# 02_PCIE.net
KiCad netlist of a schematic drawn in Altium Designer
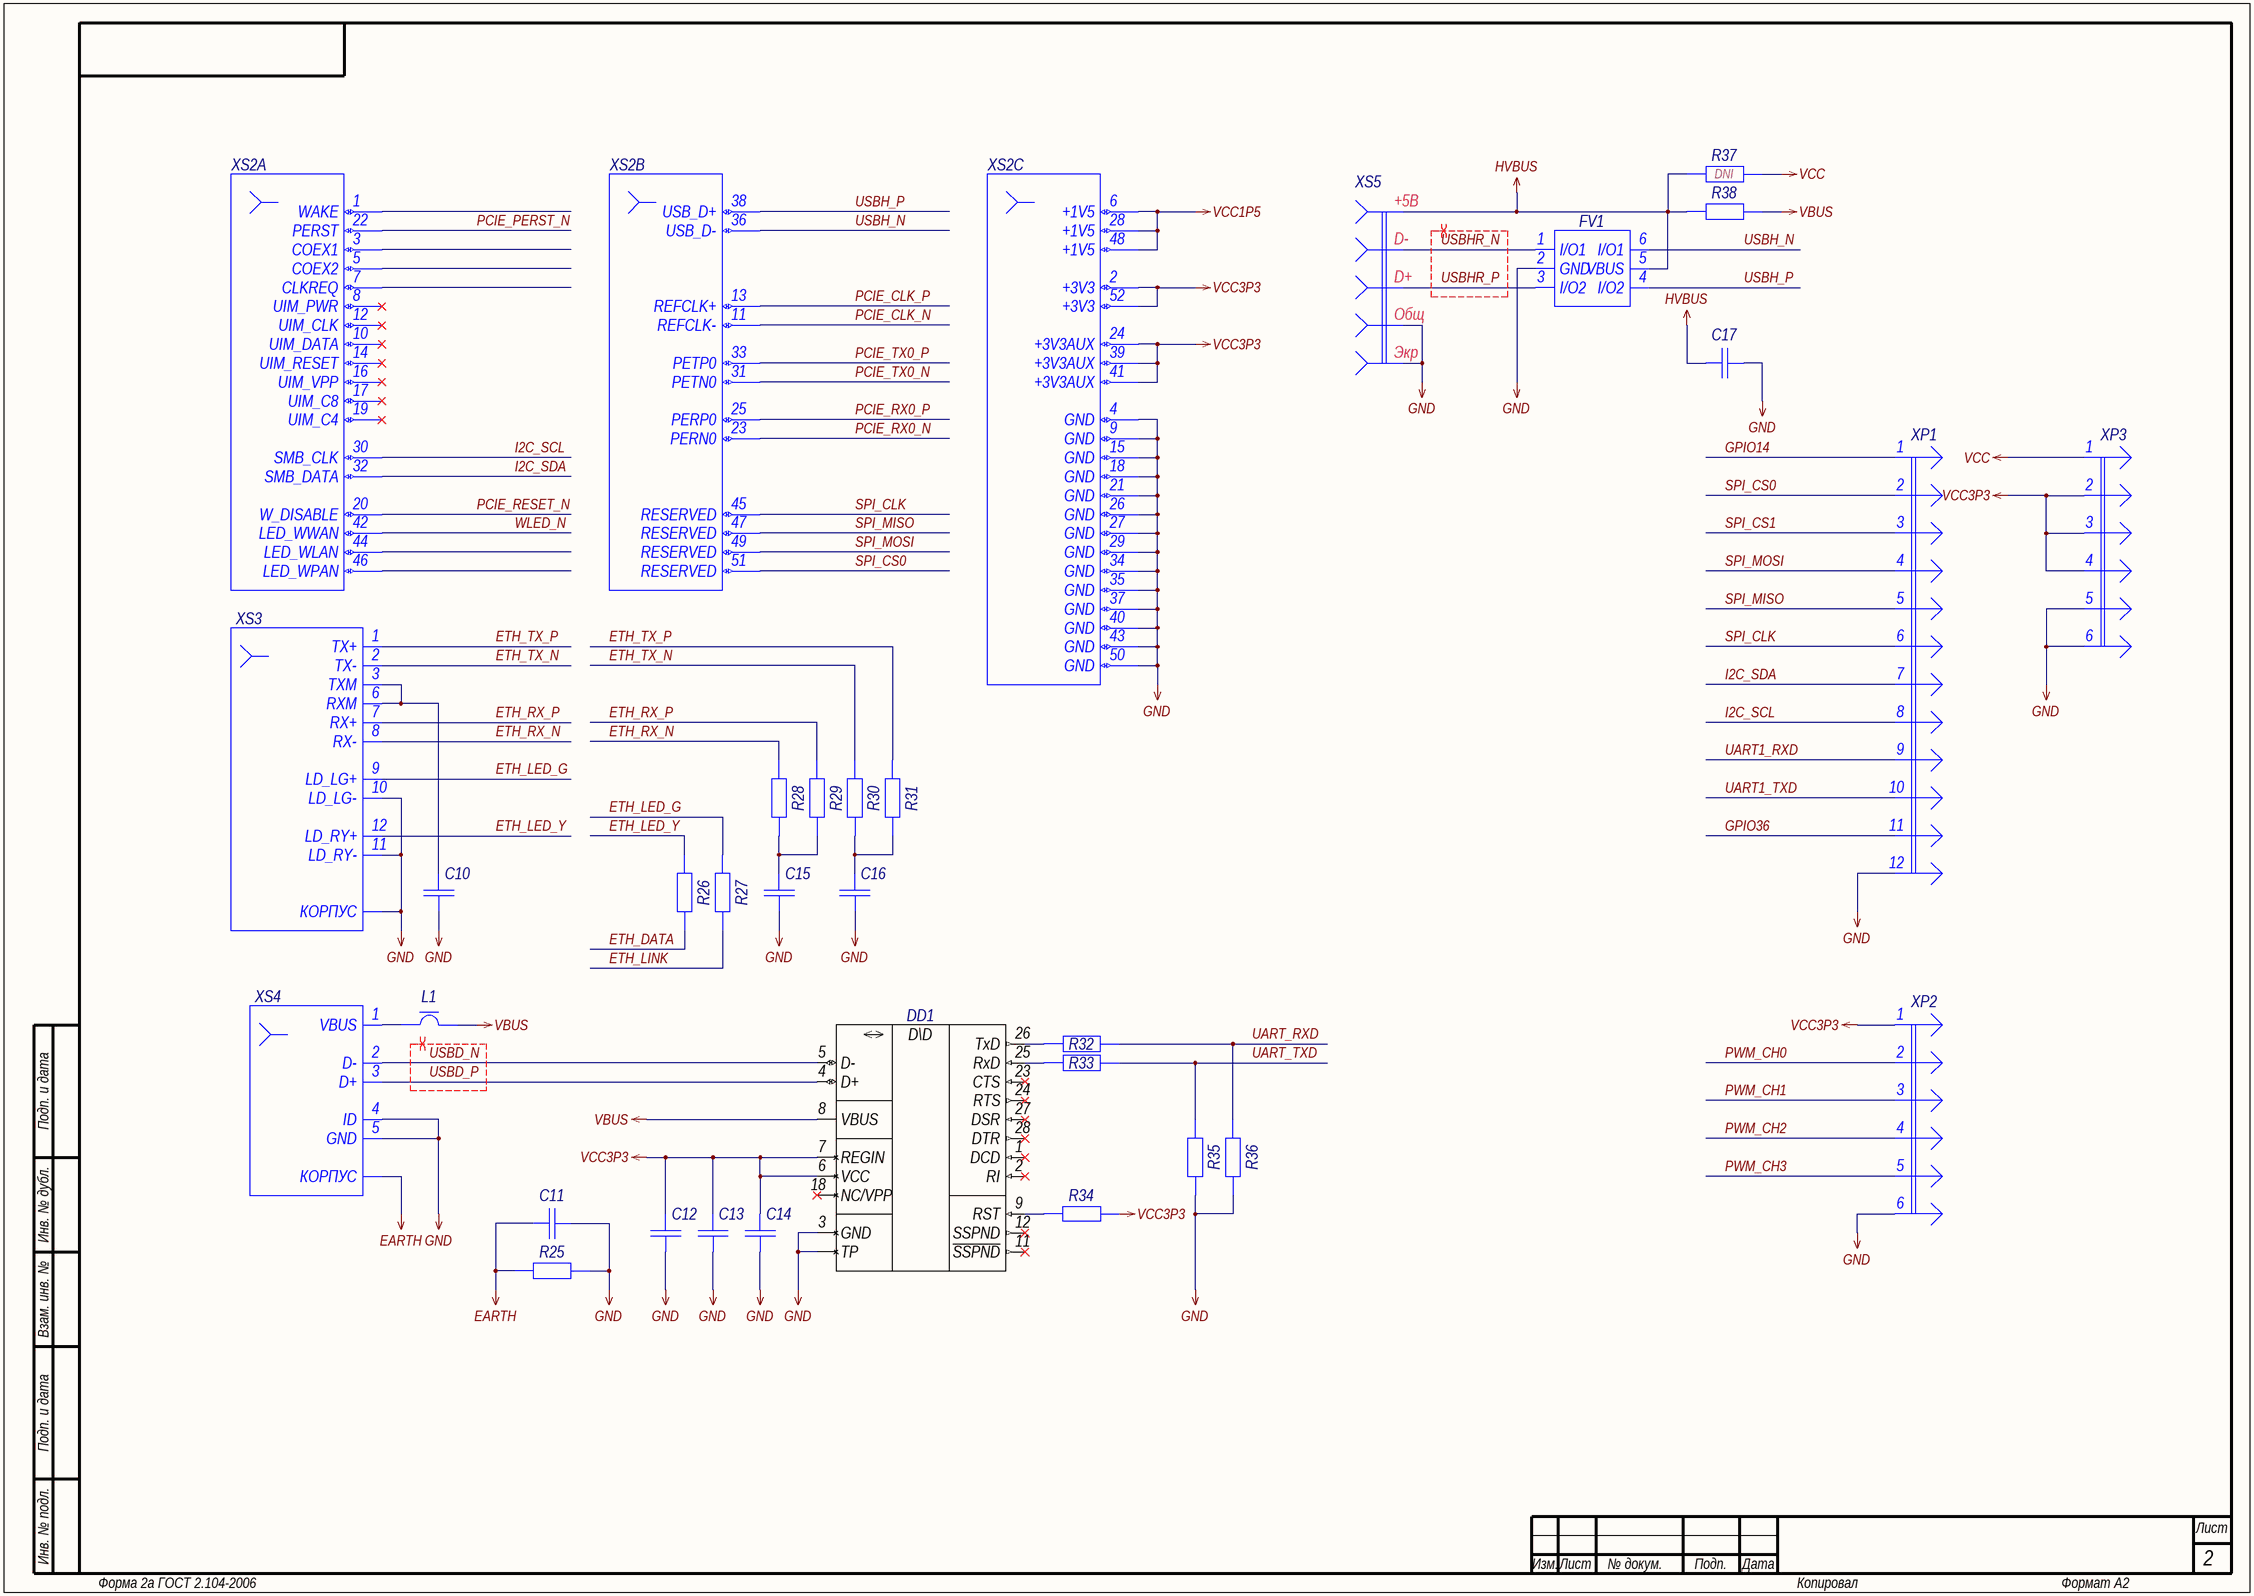
[diagram p0: 02_PCIE.SchDoc]

(export (version "E")
  (design (tool "Eeschema 10.0.6"))
  (components
    (comp (ref "C10")
      (value "Capacitor")
      (footprint "C0603_L")
      (fields
        (field (name "PART NUMBER") "GRM188R72A104KA35D")
        (field (name "VOLTAGE") "100V")
        (field (name "TOLERANCE") "±10%")
        (field (name "PUBLISHER") "Andrew Danich")
      )
      (libsource (lib "ADLib") (part "Capacitor"))
    )
    (comp (ref "C11")
      (value "Capacitor")
      (footprint "C0603_L")
      (fields
        (field (name "PART NUMBER") "GRM188R72A104KA35D")
        (field (name "VOLTAGE") "100V")
        (field (name "TOLERANCE") "±10%")
        (field (name "PUBLISHER") "Andrew Danich")
      )
      (libsource (lib "ADLib") (part "Capacitor"))
    )
    (comp (ref "C12")
      (value "Capacitor")
      (footprint "C0603_L")
      (fields
        (field (name "PART NUMBER") "GCM188R71E105KA64D")
        (field (name "VOLTAGE") "25V")
        (field (name "TOLERANCE") "±10%")
        (field (name "PUBLISHER") "Andrew Danich")
      )
      (libsource (lib "ADLib") (part "Capacitor"))
    )
    (comp (ref "C13")
      (value "Capacitor")
      (footprint "C0603_L")
      (fields
        (field (name "PART NUMBER") "GRM188R72A104KA35D")
        (field (name "VOLTAGE") "100V")
        (field (name "TOLERANCE") "±10%")
        (field (name "PUBLISHER") "Andrew Danich")
      )
      (libsource (lib "ADLib") (part "Capacitor"))
    )
    (comp (ref "C14")
      (value "Capacitor")
      (footprint "C0603_L")
      (fields
        (field (name "PART NUMBER") "GRM188R72A104KA35D")
        (field (name "VOLTAGE") "100V")
        (field (name "TOLERANCE") "±10%")
        (field (name "PUBLISHER") "Andrew Danich")
      )
      (libsource (lib "ADLib") (part "Capacitor"))
    )
    (comp (ref "C15")
      (value "Capacitor")
      (footprint "C0603_L")
      (fields
        (field (name "PART NUMBER") "GRM188R72A104KA35D")
        (field (name "VOLTAGE") "100V")
        (field (name "TOLERANCE") "±10%")
        (field (name "PUBLISHER") "Andrew Danich")
      )
      (libsource (lib "ADLib") (part "Capacitor"))
    )
    (comp (ref "C16")
      (value "Capacitor")
      (footprint "C0603_L")
      (fields
        (field (name "PART NUMBER") "GRM188R72A104KA35D")
        (field (name "VOLTAGE") "100V")
        (field (name "TOLERANCE") "±10%")
        (field (name "PUBLISHER") "Andrew Danich")
      )
      (libsource (lib "ADLib") (part "Capacitor"))
    )
    (comp (ref "C17")
      (value "Capacitor")
      (footprint "C0603_L")
      (fields
        (field (name "PART NUMBER") "GRM188R61A106KE69D")
        (field (name "VOLTAGE") "10V")
        (field (name "TOLERANCE") "±10%")
        (field (name "PUBLISHER") "Andrew Danich")
      )
      (libsource (lib "ADLib") (part "Capacitor"))
    )
    (comp (ref "DD1")
      (value "CP2102_9")
      (footprint "QFN-28_050P500X500X100_N")
      (description "Single Chip USB to UART Bridge")
      (fields
        (field (name "PART NUMBER") "CP2102-GM")
        (field (name "MANUFACTURER") "Silicon Labs")
        (field (name "PUBLISHER") "Andrew Danich")
      )
      (libsource (lib "ADLib") (part "CP2102_9"))
    )
    (comp (ref "FV1")
      (value "USBLC6-2SC6")
      (footprint "SOT-23-6_095P290X160X145_N")
      (fields (field (name "MANUFACTURER") "STMicroelectronics") (field (name "PUBLISHER") "Andrew Danich"))
      (libsource (lib "ADLib") (part "USBLC6-2SC6"))
    )
    (comp (ref "L1")
      (value "FerriteBead")
      (footprint "L0805_L")
      (fields
        (field (name "PART NUMBER") "BLM21PG331SN1")
        (field (name "TOLERANCE") "±25%")
        (field (name "MANUFACTURER") "Murata")
        (field (name "PUBLISHER") "Andrew Danich")
      )
      (libsource (lib "ADLib") (part "FerriteBead"))
    )
    (comp (ref "R25")
      (value "Resistor")
      (footprint "R0603_L")
      (fields
        (field (name "PART NUMBER") "RC0603JR-07100KL")
        (field (name "TOLERANCE") "±5%")
        (field (name "MANUFACTURER") "Yageo")
        (field (name "PUBLISHER") "Andrew Danich")
      )
      (libsource (lib "ADLib") (part "Resistor"))
    )
    (comp (ref "R26")
      (value "Resistor")
      (footprint "R0603_L")
      (fields
        (field (name "PART NUMBER") "RC0603JR-07330RL")
        (field (name "TOLERANCE") "±5%")
        (field (name "MANUFACTURER") "Yageo")
        (field (name "PUBLISHER") "Andrew Danich")
      )
      (libsource (lib "ADLib") (part "Resistor"))
    )
    (comp (ref "R27")
      (value "Resistor")
      (footprint "R0603_L")
      (fields
        (field (name "PART NUMBER") "RC0603JR-07330RL")
        (field (name "TOLERANCE") "±5%")
        (field (name "MANUFACTURER") "Yageo")
        (field (name "PUBLISHER") "Andrew Danich")
      )
      (libsource (lib "ADLib") (part "Resistor"))
    )
    (comp (ref "R28")
      (value "Resistor")
      (footprint "R0603_L")
      (fields
        (field (name "PART NUMBER") "RC0603FR-0749R9L")
        (field (name "TOLERANCE") "±1%")
        (field (name "MANUFACTURER") "Yageo")
        (field (name "PUBLISHER") "Andrew Danich")
      )
      (libsource (lib "ADLib") (part "Resistor"))
    )
    (comp (ref "R29")
      (value "Resistor")
      (footprint "R0603_L")
      (fields
        (field (name "PART NUMBER") "RC0603FR-0749R9L")
        (field (name "TOLERANCE") "±1%")
        (field (name "MANUFACTURER") "Yageo")
        (field (name "PUBLISHER") "Andrew Danich")
      )
      (libsource (lib "ADLib") (part "Resistor"))
    )
    (comp (ref "R30")
      (value "Resistor")
      (footprint "R0603_L")
      (fields
        (field (name "PART NUMBER") "RC0603FR-0749R9L")
        (field (name "TOLERANCE") "±1%")
        (field (name "MANUFACTURER") "Yageo")
        (field (name "PUBLISHER") "Andrew Danich")
      )
      (libsource (lib "ADLib") (part "Resistor"))
    )
    (comp (ref "R31")
      (value "Resistor")
      (footprint "R0603_L")
      (fields
        (field (name "PART NUMBER") "RC0603FR-0749R9L")
        (field (name "TOLERANCE") "±1%")
        (field (name "MANUFACTURER") "Yageo")
        (field (name "PUBLISHER") "Andrew Danich")
      )
      (libsource (lib "ADLib") (part "Resistor"))
    )
    (comp (ref "R32")
      (value "Resistor")
      (footprint "R0603_L")
      (fields
        (field (name "PART NUMBER") "RC0603JR-071KL")
        (field (name "TOLERANCE") "±5%")
        (field (name "MANUFACTURER") "Yageo")
        (field (name "PUBLISHER") "Andrew Danich")
      )
      (libsource (lib "ADLib") (part "Resistor"))
    )
    (comp (ref "R33")
      (value "Resistor")
      (footprint "R0603_L")
      (fields
        (field (name "PART NUMBER") "RC0603JR-071KL")
        (field (name "TOLERANCE") "±5%")
        (field (name "MANUFACTURER") "Yageo")
        (field (name "PUBLISHER") "Andrew Danich")
      )
      (libsource (lib "ADLib") (part "Resistor"))
    )
    (comp (ref "R34")
      (value "Resistor")
      (footprint "R0603_L")
      (fields
        (field (name "PART NUMBER") "RC0603JR-074K7L")
        (field (name "TOLERANCE") "±5%")
        (field (name "MANUFACTURER") "Yageo")
        (field (name "PUBLISHER") "Andrew Danich")
      )
      (libsource (lib "ADLib") (part "Resistor"))
    )
    (comp (ref "R35")
      (value "Resistor")
      (footprint "R0603_L")
      (fields
        (field (name "PART NUMBER") "RC0603JR-073KL")
        (field (name "TOLERANCE") "±5%")
        (field (name "MANUFACTURER") "Yageo")
        (field (name "PUBLISHER") "Andrew Danich")
      )
      (libsource (lib "ADLib") (part "Resistor"))
    )
    (comp (ref "R36")
      (value "Resistor")
      (footprint "R0603_L")
      (fields
        (field (name "PART NUMBER") "RC0603JR-073KL")
        (field (name "TOLERANCE") "±5%")
        (field (name "MANUFACTURER") "Yageo")
        (field (name "PUBLISHER") "Andrew Danich")
      )
      (libsource (lib "ADLib") (part "Resistor"))
    )
    (comp (ref "R37")
      (value "Resistor")
      (footprint "R0603_L")
      (fields
        (field (name "PART NUMBER") "RC0603JR-070R")
        (field (name "TOLERANCE") "±5%")
        (field (name "MANUFACTURER") "Yageo")
        (field (name "PUBLISHER") "Andrew Danich")
      )
      (libsource (lib "ADLib") (part "Resistor"))
    )
    (comp (ref "R38")
      (value "Resistor")
      (footprint "R0603_L")
      (fields
        (field (name "PART NUMBER") "RC0603JR-070R")
        (field (name "TOLERANCE") "±5%")
        (field (name "MANUFACTURER") "Yageo")
        (field (name "PUBLISHER") "Andrew Danich")
      )
      (libsource (lib "ADLib") (part "Resistor"))
    )
    (comp (ref "XP1")
      (value "IO")
      (footprint "PLS-12")
      (fields (field (name "PART NUMBER") "PLS-12") (field (name "PUBLISHER") "Andrew Danich"))
      (libsource (lib "ADLib") (part "Con-12-M"))
    )
    (comp (ref "XP2")
      (value "POWER")
      (footprint "PLS-6")
      (fields (field (name "PART NUMBER") "PLS-6") (field (name "PUBLISHER") "Andrew Danich"))
      (libsource (lib "ADLib") (part "Con-6-M"))
    )
    (comp (ref "XP3")
      (value "POWER")
      (footprint "PLS-6")
      (fields (field (name "PART NUMBER") "PLS-6") (field (name "PUBLISHER") "Andrew Danich"))
      (libsource (lib "ADLib") (part "Con-6-M"))
    )
    (comp (ref "XS2")
      (value "Text")
      (footprint "2041119-2")
      (fields
        (field (name "PART NUMBER") "2041119-2")
        (field (name "MANUFACTURER") "TE Connectivity")
        (field (name "PUBLISHER") "Andrew Danich")
      )
      (libsource (lib "ADLib") (part "mPCI-E"))
    )
    (comp (ref "XS3")
      (value "ETH")
      (footprint "SK02-111006NL")
      (fields
        (field (name "PART NUMBER") "SK02-111006NL")
        (field (name "MANUFACTURER") "Sanken Electric Co., Ltd")
        (field (name "PUBLISHER") "Andrew Danich")
      )
      (libsource (lib "ADLib") (part "SK02-111006NL"))
    )
    (comp (ref "XS4")
      (value "Text")
      (footprint "A01SB141B1-067")
      (fields
        (field (name "PART NUMBER") "A01SB141B1-067")
        (field (name "MANUFACTURER") "Jing Extension of the Electronic Co")
        (field (name "PUBLISHER") "Andrew Danich")
      )
      (libsource (lib "ADLib") (part "Con-5-F-microUSB"))
    )
    (comp (ref "XS5")
      (value "Text")
      (footprint "DS1095")
      (fields
        (field (name "PART NUMBER") "DS1095-B-R")
        (field (name "MANUFACTURER") "Connfly Electronic Co., Ltd")
        (field (name "PUBLISHER") "Andrew Danich")
      )
      (libsource (lib "ADLib") (part "Con-5-F-USB"))
    )
  )
  (nets
    (net (code "1") (name "/ETH_DATA") (class "Default")
      (node (ref "R26") (pin "1") (pinfunction "1_1") (pintype "passive"))
    )
    (net (code "2") (name "/ETH_LED_G") (class "Default")
      (node (ref "R27") (pin "2") (pinfunction "2_2") (pintype "passive"))
      (node (ref "XS3") (pin "9") (pinfunction "LD_LG+_9") (pintype "passive"))
    )
    (net (code "3") (name "/ETH_LED_Y") (class "Default")
      (node (ref "R26") (pin "2") (pinfunction "2_2") (pintype "passive"))
      (node (ref "XS3") (pin "12") (pinfunction "LD_RY+_12") (pintype "passive"))
    )
    (net (code "4") (name "/ETH_LINK") (class "Default")
      (node (ref "R27") (pin "1") (pinfunction "1_1") (pintype "passive"))
    )
    (net (code "5") (name "/ETH_RX_N") (class "Default")
      (node (ref "R28") (pin "2") (pinfunction "2_2") (pintype "passive"))
      (node (ref "XS3") (pin "8") (pinfunction "RX-_8") (pintype "passive"))
    )
    (net (code "6") (name "/ETH_RX_P") (class "Default")
      (node (ref "R29") (pin "2") (pinfunction "2_2") (pintype "passive"))
      (node (ref "XS3") (pin "7") (pinfunction "RX+_7") (pintype "passive"))
    )
    (net (code "7") (name "/ETH_TX_N") (class "Default")
      (node (ref "R30") (pin "2") (pinfunction "2_2") (pintype "passive"))
      (node (ref "XS3") (pin "2") (pinfunction "TX-_2") (pintype "passive"))
    )
    (net (code "8") (name "/ETH_TX_P") (class "Default")
      (node (ref "R31") (pin "2") (pinfunction "2_2") (pintype "passive"))
      (node (ref "XS3") (pin "1") (pinfunction "TX+_1") (pintype "passive"))
    )
    (net (code "9") (name "/GPIO14") (class "Default") (node (ref "XP1") (pin "1") (pintype "passive")))
    (net (code "10") (name "/GPIO36") (class "Default") (node (ref "XP1") (pin "11") (pintype "passive")))
    (net (code "11") (name "/I2C_SCL") (class "Default")
      (node (ref "XP1") (pin "8") (pintype "passive"))
      (node (ref "XS2") (pin "30") (pinfunction "SMB_CLK_30") (pintype "bidirectional"))
    )
    (net (code "12") (name "/I2C_SDA") (class "Default")
      (node (ref "XP1") (pin "7") (pintype "passive"))
      (node (ref "XS2") (pin "32") (pinfunction "SMB_DATA_32") (pintype "bidirectional"))
    )
    (net (code "13") (name "/PCIE_CLK_N") (class "Default")
      (node (ref "XS2") (pin "11") (pinfunction "REFCLK-_11") (pintype "bidirectional"))
    )
    (net (code "14") (name "/PCIE_CLK_P") (class "Default")
      (node (ref "XS2") (pin "13") (pinfunction "REFCLK+_13") (pintype "bidirectional"))
    )
    (net (code "15") (name "/PCIE_PERST_N") (class "Default")
      (node (ref "XS2") (pin "22") (pinfunction "PERST_22") (pintype "bidirectional"))
    )
    (net (code "16") (name "/PCIE_RESET_N") (class "Default")
      (node (ref "XS2") (pin "20") (pinfunction "W_DISABLE_20") (pintype "bidirectional"))
    )
    (net (code "17") (name "/PCIE_RX0_N") (class "Default")
      (node (ref "XS2") (pin "23") (pinfunction "PERN0_23") (pintype "bidirectional"))
    )
    (net (code "18") (name "/PCIE_RX0_P") (class "Default")
      (node (ref "XS2") (pin "25") (pinfunction "PERP0_25") (pintype "bidirectional"))
    )
    (net (code "19") (name "/PCIE_TX0_N") (class "Default")
      (node (ref "XS2") (pin "31") (pinfunction "PETN0_31") (pintype "bidirectional"))
    )
    (net (code "20") (name "/PCIE_TX0_P") (class "Default")
      (node (ref "XS2") (pin "33") (pinfunction "PETP0_33") (pintype "bidirectional"))
    )
    (net (code "21") (name "/PWM_CH0") (class "Default") (node (ref "XP2") (pin "2") (pintype "passive")))
    (net (code "22") (name "/PWM_CH1") (class "Default") (node (ref "XP2") (pin "3") (pintype "passive")))
    (net (code "23") (name "/PWM_CH2") (class "Default") (node (ref "XP2") (pin "4") (pintype "passive")))
    (net (code "24") (name "/PWM_CH3") (class "Default") (node (ref "XP2") (pin "5") (pintype "passive")))
    (net (code "25") (name "/SPI_CLK") (class "Default")
      (node (ref "XP1") (pin "6") (pintype "passive"))
      (node (ref "XS2") (pin "45") (pinfunction "RESERVED_45") (pintype "bidirectional"))
    )
    (net (code "26") (name "/SPI_CS0") (class "Default")
      (node (ref "XP1") (pin "2") (pintype "passive"))
      (node (ref "XS2") (pin "51") (pinfunction "RESERVED_51") (pintype "bidirectional"))
    )
    (net (code "27") (name "/SPI_CS1") (class "Default") (node (ref "XP1") (pin "3") (pintype "passive")))
    (net (code "28") (name "/SPI_MISO") (class "Default")
      (node (ref "XP1") (pin "5") (pintype "passive"))
      (node (ref "XS2") (pin "47") (pinfunction "RESERVED_47") (pintype "bidirectional"))
    )
    (net (code "29") (name "/SPI_MOSI") (class "Default")
      (node (ref "XP1") (pin "4") (pintype "passive"))
      (node (ref "XS2") (pin "49") (pinfunction "RESERVED_49") (pintype "bidirectional"))
    )
    (net (code "30") (name "/UART1_RXD") (class "Default") (node (ref "XP1") (pin "9") (pintype "passive")))
    (net (code "31") (name "/UART1_TXD") (class "Default") (node (ref "XP1") (pin "10") (pintype "passive")))
    (net (code "32") (name "/UART_RXD") (class "Default")
      (node (ref "R32") (pin "2") (pinfunction "2_2") (pintype "passive"))
      (node (ref "R36") (pin "2") (pinfunction "2_2") (pintype "passive"))
    )
    (net (code "33") (name "/UART_TXD") (class "Default")
      (node (ref "R33") (pin "2") (pinfunction "2_2") (pintype "passive"))
      (node (ref "R35") (pin "2") (pinfunction "2_2") (pintype "passive"))
    )
    (net (code "34") (name "/USBD_N") (class "Default")
      (node (ref "DD1") (pin "5") (pinfunction "D-_5") (pintype "bidirectional"))
      (node (ref "XS4") (pin "2") (pinfunction "D-_2") (pintype "passive"))
    )
    (net (code "35") (name "/USBD_P") (class "Default")
      (node (ref "DD1") (pin "4") (pinfunction "D+_4") (pintype "bidirectional"))
      (node (ref "XS4") (pin "3") (pinfunction "D+_3") (pintype "passive"))
    )
    (net (code "36") (name "/USBHR_N") (class "Default")
      (node (ref "FV1") (pin "1") (pinfunction "I/O1_1") (pintype "passive"))
      (node (ref "XS5") (pin "2") (pintype "passive"))
    )
    (net (code "37") (name "/USBHR_P") (class "Default")
      (node (ref "FV1") (pin "3") (pinfunction "I/O2_3") (pintype "passive"))
      (node (ref "XS5") (pin "3") (pintype "passive"))
    )
    (net (code "38") (name "/USBH_N") (class "Default")
      (node (ref "FV1") (pin "6") (pinfunction "I/O1_6") (pintype "passive"))
      (node (ref "XS2") (pin "36") (pinfunction "USB_D-_36") (pintype "bidirectional"))
    )
    (net (code "39") (name "/USBH_P") (class "Default")
      (node (ref "FV1") (pin "4") (pinfunction "I/O2_4") (pintype "passive"))
      (node (ref "XS2") (pin "38") (pinfunction "USB_D+_38") (pintype "bidirectional"))
    )
    (net (code "40") (name "/WLED_N") (class "Default")
      (node (ref "XS2") (pin "42") (pinfunction "LED_WWAN_42") (pintype "bidirectional"))
    )
    (net (code "41") (name "EARTH") (class "Default")
      (node (ref "C11") (pin "2") (pinfunction "2_2") (pintype "passive"))
      (node (ref "R25") (pin "1") (pinfunction "1_1") (pintype "passive"))
      (node (ref "XS4") (pin "SHELL") (pinfunction "КОРПУС_SHELL") (pintype "passive"))
    )
    (net (code "42") (name "GND") (class "Default")
      (node (ref "C10") (pin "1") (pinfunction "1_1") (pintype "passive"))
      (node (ref "C11") (pin "1") (pinfunction "1_1") (pintype "passive"))
      (node (ref "C12") (pin "1") (pinfunction "1_1") (pintype "passive"))
      (node (ref "C13") (pin "1") (pinfunction "1_1") (pintype "passive"))
      (node (ref "C14") (pin "1") (pinfunction "1_1") (pintype "passive"))
      (node (ref "C15") (pin "1") (pinfunction "1_1") (pintype "passive"))
      (node (ref "C16") (pin "1") (pinfunction "1_1") (pintype "passive"))
      (node (ref "C17") (pin "2") (pinfunction "2_2") (pintype "passive"))
      (node (ref "DD1") (pin "3") (pinfunction "GND_3") (pintype "power_in"))
      (node (ref "DD1") (pin "TP") (pinfunction "TP_TP") (pintype "power_in"))
      (node (ref "FV1") (pin "2") (pinfunction "GND_2") (pintype "passive"))
      (node (ref "R25") (pin "2") (pinfunction "2_2") (pintype "passive"))
      (node (ref "R35") (pin "1") (pinfunction "1_1") (pintype "passive"))
      (node (ref "R36") (pin "1") (pinfunction "1_1") (pintype "passive"))
      (node (ref "XP1") (pin "12") (pintype "passive"))
      (node (ref "XP2") (pin "6") (pintype "passive"))
      (node (ref "XP3") (pin "5") (pintype "passive"))
      (node (ref "XP3") (pin "6") (pintype "passive"))
      (node (ref "XS2") (pin "15") (pinfunction "GND_15") (pintype "bidirectional"))
      (node (ref "XS2") (pin "18") (pinfunction "GND_18") (pintype "bidirectional"))
      (node (ref "XS2") (pin "21") (pinfunction "GND_21") (pintype "bidirectional"))
      (node (ref "XS2") (pin "26") (pinfunction "GND_26") (pintype "bidirectional"))
      (node (ref "XS2") (pin "27") (pinfunction "GND_27") (pintype "bidirectional"))
      (node (ref "XS2") (pin "29") (pinfunction "GND_29") (pintype "bidirectional"))
      (node (ref "XS2") (pin "34") (pinfunction "GND_34") (pintype "bidirectional"))
      (node (ref "XS2") (pin "35") (pinfunction "GND_35") (pintype "bidirectional"))
      (node (ref "XS2") (pin "37") (pinfunction "GND_37") (pintype "bidirectional"))
      (node (ref "XS2") (pin "4") (pinfunction "GND_4") (pintype "bidirectional"))
      (node (ref "XS2") (pin "40") (pinfunction "GND_40") (pintype "bidirectional"))
      (node (ref "XS2") (pin "43") (pinfunction "GND_43") (pintype "bidirectional"))
      (node (ref "XS2") (pin "50") (pinfunction "GND_50") (pintype "bidirectional"))
      (node (ref "XS2") (pin "9") (pinfunction "GND_9") (pintype "bidirectional"))
      (node (ref "XS3") (pin "10") (pinfunction "LD_LG-_10") (pintype "passive"))
      (node (ref "XS3") (pin "11") (pinfunction "LD_RY-_11") (pintype "passive"))
      (node (ref "XS3") (pin "CASE") (pinfunction "КОРПУС_CASE") (pintype "passive"))
      (node (ref "XS4") (pin "4") (pinfunction "ID_4") (pintype "passive"))
      (node (ref "XS4") (pin "5") (pinfunction "GND_5") (pintype "passive"))
      (node (ref "XS5") (pin "4") (pintype "passive"))
      (node (ref "XS5") (pin "5") (pintype "passive"))
    )
    (net (code "43") (name "HVBUS") (class "Default")
      (node (ref "C17") (pin "1") (pinfunction "1_1") (pintype "passive"))
      (node (ref "FV1") (pin "5") (pinfunction "VBUS_5") (pintype "passive"))
      (node (ref "R37") (pin "1") (pinfunction "1_1") (pintype "passive"))
      (node (ref "R38") (pin "1") (pinfunction "1_1") (pintype "passive"))
      (node (ref "XS5") (pin "1") (pintype "passive"))
    )
    (net (code "44") (name "Net-(C15-Pad2)") (class "Default")
      (node (ref "C15") (pin "2") (pinfunction "2_2") (pintype "passive"))
      (node (ref "R28") (pin "1") (pinfunction "1_1") (pintype "passive"))
      (node (ref "R29") (pin "1") (pinfunction "1_1") (pintype "passive"))
    )
    (net (code "45") (name "Net-(C16-Pad2)") (class "Default")
      (node (ref "C16") (pin "2") (pinfunction "2_2") (pintype "passive"))
      (node (ref "R30") (pin "1") (pinfunction "1_1") (pintype "passive"))
      (node (ref "R31") (pin "1") (pinfunction "1_1") (pintype "passive"))
    )
    (net (code "46") (name "Net-(DD1-RST)") (class "Default")
      (node (ref "DD1") (pin "9") (pinfunction "RST_9") (pintype "input"))
      (node (ref "R34") (pin "2") (pinfunction "2_2") (pintype "passive"))
    )
    (net (code "47") (name "Net-(DD1-RxD)") (class "Default")
      (node (ref "DD1") (pin "25") (pinfunction "RxD_25") (pintype "input"))
      (node (ref "R33") (pin "1") (pinfunction "1_1") (pintype "passive"))
    )
    (net (code "48") (name "Net-(DD1-TxD)") (class "Default")
      (node (ref "DD1") (pin "26") (pinfunction "TxD_26") (pintype "output"))
      (node (ref "R32") (pin "1") (pinfunction "1_1") (pintype "passive"))
    )
    (net (code "49") (name "Net-(XS3-RXM)") (class "Default")
      (node (ref "C10") (pin "2") (pinfunction "2_2") (pintype "passive"))
      (node (ref "XS3") (pin "3") (pinfunction "TXM_3") (pintype "passive"))
      (node (ref "XS3") (pin "6") (pinfunction "RXM_6") (pintype "passive"))
    )
    (net (code "50") (name "Net-(XS4-VBUS)") (class "Default")
      (node (ref "L1") (pin "1") (pinfunction "1_1") (pintype "passive"))
      (node (ref "XS4") (pin "1") (pinfunction "VBUS_1") (pintype "passive"))
    )
    (net (code "51") (name "VBUS") (class "Default")
      (node (ref "DD1") (pin "8") (pinfunction "VBUS_8") (pintype "power_in"))
      (node (ref "L1") (pin "2") (pinfunction "2_2") (pintype "passive"))
      (node (ref "R38") (pin "2") (pinfunction "2_2") (pintype "passive"))
    )
    (net (code "52") (name "VCC") (class "Default")
      (node (ref "R37") (pin "2") (pinfunction "2_2") (pintype "passive"))
      (node (ref "XP3") (pin "1") (pintype "passive"))
    )
    (net (code "53") (name "VCC1P5") (class "Default")
      (node (ref "XS2") (pin "28") (pinfunction "+1V5_28") (pintype "bidirectional"))
      (node (ref "XS2") (pin "48") (pinfunction "+1V5_48") (pintype "bidirectional"))
      (node (ref "XS2") (pin "6") (pinfunction "+1V5_6") (pintype "bidirectional"))
    )
    (net (code "54") (name "VCC3P3") (class "Default")
      (node (ref "C12") (pin "2") (pinfunction "2_2") (pintype "passive"))
      (node (ref "C13") (pin "2") (pinfunction "2_2") (pintype "passive"))
      (node (ref "C14") (pin "2") (pinfunction "2_2") (pintype "passive"))
      (node (ref "DD1") (pin "6") (pinfunction "VCC_6") (pintype "power_in"))
      (node (ref "DD1") (pin "7") (pinfunction "REGIN_7") (pintype "power_in"))
      (node (ref "R34") (pin "1") (pinfunction "1_1") (pintype "passive"))
      (node (ref "XP2") (pin "1") (pintype "passive"))
      (node (ref "XP3") (pin "2") (pintype "passive"))
      (node (ref "XP3") (pin "3") (pintype "passive"))
      (node (ref "XP3") (pin "4") (pintype "passive"))
      (node (ref "XS2") (pin "2") (pinfunction "+3V3_2") (pintype "bidirectional"))
      (node (ref "XS2") (pin "24") (pinfunction "+3V3AUX_24") (pintype "bidirectional"))
      (node (ref "XS2") (pin "39") (pinfunction "+3V3AUX_39") (pintype "bidirectional"))
      (node (ref "XS2") (pin "41") (pinfunction "+3V3AUX_41") (pintype "bidirectional"))
      (node (ref "XS2") (pin "52") (pinfunction "+3V3_52") (pintype "bidirectional"))
    )
    (net (code "55") (name "unconnected-(DD1-CTS-Pad23)") (class "Default")
      (node (ref "DD1") (pin "23") (pinfunction "CTS_23") (pintype "input+no_connect"))
    )
    (net (code "56") (name "unconnected-(DD1-DCD-Pad1)") (class "Default")
      (node (ref "DD1") (pin "1") (pinfunction "DCD_1") (pintype "input+no_connect"))
    )
    (net (code "57") (name "unconnected-(DD1-DSR-Pad27)") (class "Default")
      (node (ref "DD1") (pin "27") (pinfunction "DSR_27") (pintype "input+no_connect"))
    )
    (net (code "58") (name "unconnected-(DD1-DTR-Pad28)") (class "Default")
      (node (ref "DD1") (pin "28") (pinfunction "DTR_28") (pintype "output+no_connect"))
    )
    (net (code "59") (name "unconnected-(DD1-NC{slash}VPP-Pad18)") (class "Default")
      (node (ref "DD1") (pin "18") (pinfunction "NC/VPP_18") (pintype "power_in+no_connect"))
    )
    (net (code "60") (name "unconnected-(DD1-RI-Pad2)") (class "Default")
      (node (ref "DD1") (pin "2") (pinfunction "RI_2") (pintype "input+no_connect"))
    )
    (net (code "61") (name "unconnected-(DD1-RTS-Pad24)") (class "Default")
      (node (ref "DD1") (pin "24") (pinfunction "RTS_24") (pintype "output+no_connect"))
    )
    (net (code "62") (name "unconnected-(DD1-SSPND-Pad12)") (class "Default")
      (node (ref "DD1") (pin "12") (pinfunction "SSPND_12") (pintype "output+no_connect"))
    )
    (net (code "63") (name "unconnected-(DD1-~{SSPND}-Pad11)") (class "Default")
      (node (ref "DD1") (pin "11") (pinfunction "~{SSPND}_11") (pintype "output+no_connect"))
    )
    (net (code "64") (name "unconnected-(XS2A-CLKREQ-Pad7)") (class "Default")
      (node (ref "XS2") (pin "7") (pinfunction "CLKREQ_7") (pintype "bidirectional"))
    )
    (net (code "65") (name "unconnected-(XS2A-COEX1-Pad3)") (class "Default")
      (node (ref "XS2") (pin "3") (pinfunction "COEX1_3") (pintype "bidirectional"))
    )
    (net (code "66") (name "unconnected-(XS2A-COEX2-Pad5)") (class "Default")
      (node (ref "XS2") (pin "5") (pinfunction "COEX2_5") (pintype "bidirectional"))
    )
    (net (code "67") (name "unconnected-(XS2A-LED_WLAN-Pad44)") (class "Default")
      (node (ref "XS2") (pin "44") (pinfunction "LED_WLAN_44") (pintype "bidirectional"))
    )
    (net (code "68") (name "unconnected-(XS2A-LED_WPAN-Pad46)") (class "Default")
      (node (ref "XS2") (pin "46") (pinfunction "LED_WPAN_46") (pintype "bidirectional"))
    )
    (net (code "69") (name "unconnected-(XS2A-UIM_C4-Pad19)") (class "Default")
      (node (ref "XS2") (pin "19") (pinfunction "UIM_C4_19") (pintype "bidirectional+no_connect"))
    )
    (net (code "70") (name "unconnected-(XS2A-UIM_C8-Pad17)") (class "Default")
      (node (ref "XS2") (pin "17") (pinfunction "UIM_C8_17") (pintype "bidirectional+no_connect"))
    )
    (net (code "71") (name "unconnected-(XS2A-UIM_CLK-Pad12)") (class "Default")
      (node (ref "XS2") (pin "12") (pinfunction "UIM_CLK_12") (pintype "bidirectional+no_connect"))
    )
    (net (code "72") (name "unconnected-(XS2A-UIM_DATA-Pad10)") (class "Default")
      (node (ref "XS2") (pin "10") (pinfunction "UIM_DATA_10") (pintype "bidirectional+no_connect"))
    )
    (net (code "73") (name "unconnected-(XS2A-UIM_PWR-Pad8)") (class "Default")
      (node (ref "XS2") (pin "8") (pinfunction "UIM_PWR_8") (pintype "bidirectional+no_connect"))
    )
    (net (code "74") (name "unconnected-(XS2A-UIM_RESET-Pad14)") (class "Default")
      (node (ref "XS2") (pin "14") (pinfunction "UIM_RESET_14") (pintype "bidirectional+no_connect"))
    )
    (net (code "75") (name "unconnected-(XS2A-UIM_VPP-Pad16)") (class "Default")
      (node (ref "XS2") (pin "16") (pinfunction "UIM_VPP_16") (pintype "bidirectional+no_connect"))
    )
    (net (code "76") (name "unconnected-(XS2A-WAKE-Pad1)") (class "Default")
      (node (ref "XS2") (pin "1") (pinfunction "WAKE_1") (pintype "bidirectional"))
    )
  )
)
